# ble-v-monitor.net
KiCad netlist of a schematic drawn in EAGLE
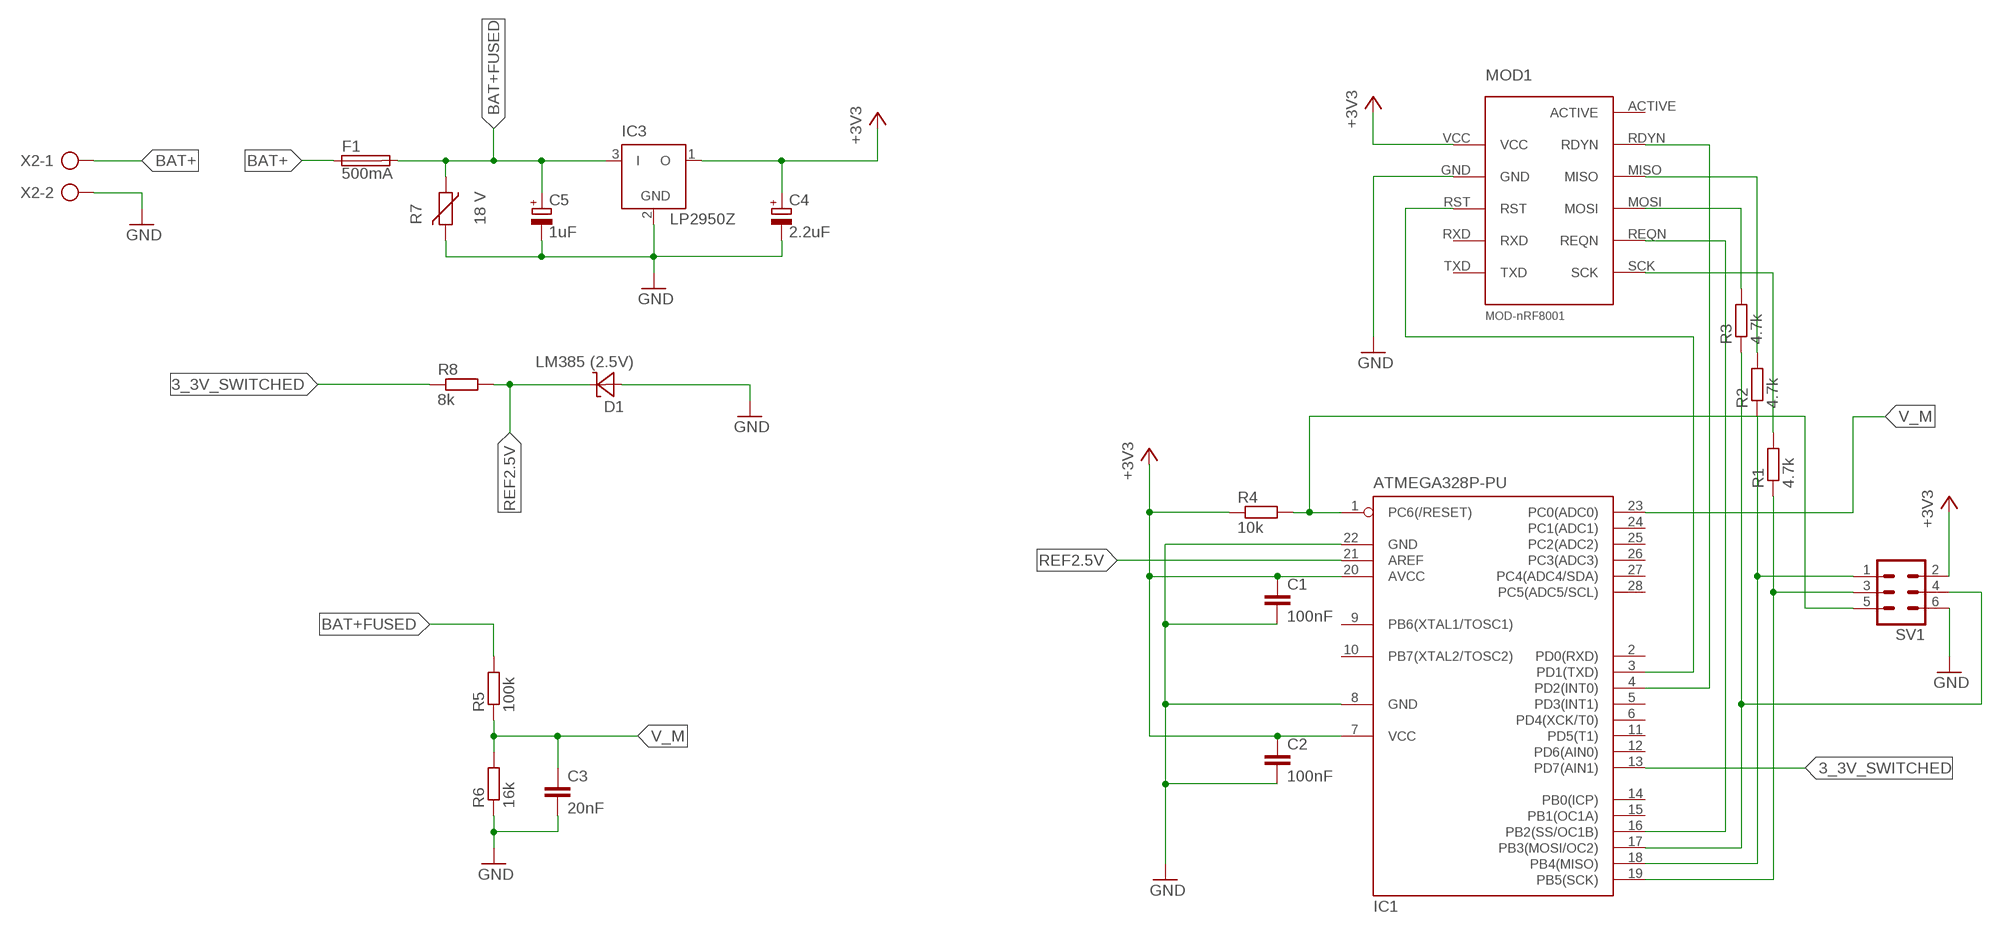
[diagram p0: schematic, sheet 1]

(export (version "E")
  (design (tool "Eeschema 10.0.6"))
  (components
    (comp (ref "C1")
      (value "100nF")
      (footprint "eagle-import:C050-024X044")
      (libsource (lib "eagle-import") (part "C-EU050-024X044"))
    )
    (comp (ref "C2")
      (value "100nF")
      (footprint "eagle-import:C050-024X044")
      (libsource (lib "eagle-import") (part "C-EU050-024X044"))
    )
    (comp (ref "C3")
      (value "20nF")
      (footprint "eagle-import:C050-024X044")
      (libsource (lib "eagle-import") (part "C-EU050-024X044"))
    )
    (comp (ref "C4")
      (value "2.2uF")
      (footprint "eagle-import:TT2D5")
      (libsource (lib "eagle-import") (part "CPOL-EUTT2D5"))
    )
    (comp (ref "C5")
      (value "1uF")
      (footprint "eagle-import:TT2D5")
      (libsource (lib "eagle-import") (part "CPOL-EUTT2D5"))
    )
    (comp (ref "D1")
      (value "LM385 (2.5V)")
      (footprint "eagle-import:TO-92")
      (libsource (lib "eagle-import") (part "LM385"))
    )
    (comp (ref "F1")
      (value "500mA")
      (footprint "eagle-import:SH22,5")
      (fields (field (name "MF") "SCHURTER") (field (name "MPN") "0031.8201"))
      (libsource (lib "eagle-import") (part "SH22,5"))
    )
    (comp (ref "IC1")
      (value "ATMEGA328P-PU")
      (footprint "eagle-import:DIL28-3")
      (libsource (lib "eagle-import") (part "MEGA8-P"))
    )
    (comp (ref "IC3")
      (value "LP2950Z")
      (footprint "eagle-import:TO92")
      (libsource (lib "eagle-import") (part "LP2950Z"))
    )
    (comp (ref "MOD1")
      (value "MOD-NRF8001MOD-NRF8001")
      (footprint "eagle-import:MOD-NRF8001")
      (libsource (lib "eagle-import") (part "MOD-NRF8001MOD-NRF8001"))
    )
    (comp (ref "R1")
      (value "4.7k")
      (footprint "eagle-import:0207_7")
      (libsource (lib "eagle-import") (part "R-EU_0207/7"))
    )
    (comp (ref "R2")
      (value "4.7k")
      (footprint "eagle-import:0207_7")
      (libsource (lib "eagle-import") (part "R-EU_0207/7"))
    )
    (comp (ref "R3")
      (value "4.7k")
      (footprint "eagle-import:0207_7")
      (libsource (lib "eagle-import") (part "R-EU_0207/7"))
    )
    (comp (ref "R4")
      (value "10k")
      (footprint "eagle-import:0207_7")
      (libsource (lib "eagle-import") (part "R-EU_0207/7"))
    )
    (comp (ref "R5")
      (value "100k")
      (footprint "eagle-import:0207_7")
      (libsource (lib "eagle-import") (part "R-EU_0207/7"))
    )
    (comp (ref "R6")
      (value "16k")
      (footprint "eagle-import:0207_7")
      (libsource (lib "eagle-import") (part "R-EU_0207/7"))
    )
    (comp (ref "R7")
      (value "18 V")
      (footprint "eagle-import:CT_CN0805")
      (libsource (lib "eagle-import") (part "VARISTORCN0805"))
    )
    (comp (ref "R8")
      (value "8k")
      (footprint "eagle-import:0207_7")
      (libsource (lib "eagle-import") (part "R-EU_0207/7"))
    )
    (comp (ref "SV1")
      (value "MA03-2")
      (footprint "eagle-import:MA03-2")
      (libsource (lib "eagle-import") (part "MA03-2"))
    )
    (comp (ref "X2")
      (value "AK500/2")
      (footprint "eagle-import:AK500_2")
      (libsource (lib "eagle-import") (part "AK500/2"))
    )
  )
  (nets
    (net (code "1") (name "+3V3") (class "Default")
      (node (ref "C1") (pin "1") (pinfunction "1_1") (pintype "passive"))
      (node (ref "C2") (pin "1") (pinfunction "1_1") (pintype "passive"))
      (node (ref "C4") (pin "+") (pinfunction "+_+") (pintype "passive"))
      (node (ref "IC1") (pin "20") (pinfunction "AVCC_20") (pintype "power_in"))
      (node (ref "IC1") (pin "7") (pinfunction "VCC_7") (pintype "power_in"))
      (node (ref "IC3") (pin "1") (pinfunction "O_1") (pintype "input"))
      (node (ref "MOD1") (pin "VCC") (pinfunction "VCC_VCC") (pintype "power_in"))
      (node (ref "R4") (pin "1") (pinfunction "1_1") (pintype "passive"))
      (node (ref "SV1") (pin "2") (pinfunction "2_2") (pintype "passive"))
    )
    (net (code "2") (name "3_3V_SWITCHED") (class "Default")
      (node (ref "IC1") (pin "13") (pinfunction "PD7(AIN1)_13") (pintype "bidirectional"))
      (node (ref "R8") (pin "1") (pinfunction "1_1") (pintype "passive"))
    )
    (net (code "3") (name "BAT+") (class "Default")
      (node (ref "F1") (pin "1") (pinfunction "1_1") (pintype "passive"))
      (node (ref "X2") (pin "1") (pinfunction "KL_1") (pintype "passive"))
    )
    (net (code "4") (name "BAT+FUSED") (class "Default")
      (node (ref "C5") (pin "+") (pinfunction "+_+") (pintype "passive"))
      (node (ref "F1") (pin "2") (pinfunction "2_2") (pintype "passive"))
      (node (ref "IC3") (pin "3") (pinfunction "I_3") (pintype "input"))
      (node (ref "R5") (pin "2") (pinfunction "2_2") (pintype "passive"))
      (node (ref "R7") (pin "1") (pinfunction "1_1") (pintype "passive"))
    )
    (net (code "5") (name "GND") (class "Default")
      (node (ref "C1") (pin "2") (pinfunction "2_2") (pintype "passive"))
      (node (ref "C2") (pin "2") (pinfunction "2_2") (pintype "passive"))
      (node (ref "C3") (pin "2") (pinfunction "2_2") (pintype "passive"))
      (node (ref "C4") (pin "-") (pinfunction "-_-") (pintype "passive"))
      (node (ref "C5") (pin "-") (pinfunction "-_-") (pintype "passive"))
      (node (ref "D1") (pin "+") (pinfunction "+_+") (pintype "passive"))
      (node (ref "IC1") (pin "22") (pinfunction "GND_22") (pintype "power_in"))
      (node (ref "IC1") (pin "8") (pinfunction "GND_8") (pintype "power_in"))
      (node (ref "IC3") (pin "2") (pinfunction "GND_2") (pintype "power_in"))
      (node (ref "MOD1") (pin "GND") (pinfunction "GND_GND") (pintype "power_in"))
      (node (ref "R6") (pin "1") (pinfunction "1_1") (pintype "passive"))
      (node (ref "R7") (pin "2") (pinfunction "2_2") (pintype "passive"))
      (node (ref "SV1") (pin "6") (pinfunction "6_6") (pintype "passive"))
      (node (ref "X2") (pin "2") (pinfunction "KL_2") (pintype "passive"))
    )
    (net (code "6") (name "Net-(IC1-PB2(SS{slash}OC1B))") (class "Default")
      (node (ref "IC1") (pin "16") (pinfunction "PB2(SS/OC1B)_16") (pintype "bidirectional"))
      (node (ref "MOD1") (pin "REQN") (pinfunction "REQN_REQN") (pintype "input"))
    )
    (net (code "7") (name "Net-(IC1-PB3(MOSI{slash}OC2))") (class "Default")
      (node (ref "IC1") (pin "17") (pinfunction "PB3(MOSI/OC2)_17") (pintype "bidirectional"))
      (node (ref "R3") (pin "1") (pinfunction "1_1") (pintype "passive"))
      (node (ref "SV1") (pin "4") (pinfunction "4_4") (pintype "passive"))
    )
    (net (code "8") (name "Net-(IC1-PB4(MISO))") (class "Default")
      (node (ref "IC1") (pin "18") (pinfunction "PB4(MISO)_18") (pintype "bidirectional"))
      (node (ref "R2") (pin "1") (pinfunction "1_1") (pintype "passive"))
      (node (ref "SV1") (pin "1") (pinfunction "1_1") (pintype "passive"))
    )
    (net (code "9") (name "Net-(IC1-PB5(SCK))") (class "Default")
      (node (ref "IC1") (pin "19") (pinfunction "PB5(SCK)_19") (pintype "bidirectional"))
      (node (ref "R1") (pin "1") (pinfunction "1_1") (pintype "passive"))
      (node (ref "SV1") (pin "3") (pinfunction "3_3") (pintype "passive"))
    )
    (net (code "10") (name "Net-(IC1-PC6({slash}RESET))") (class "Default")
      (node (ref "IC1") (pin "1") (pinfunction "PC6(/RESET)_1") (pintype "bidirectional"))
      (node (ref "R4") (pin "2") (pinfunction "2_2") (pintype "passive"))
      (node (ref "SV1") (pin "5") (pinfunction "5_5") (pintype "passive"))
    )
    (net (code "11") (name "Net-(IC1-PD1(TXD))") (class "Default")
      (node (ref "IC1") (pin "3") (pinfunction "PD1(TXD)_3") (pintype "bidirectional"))
      (node (ref "MOD1") (pin "RST") (pinfunction "RST_RST") (pintype "input"))
    )
    (net (code "12") (name "Net-(IC1-PD2(INT0))") (class "Default")
      (node (ref "IC1") (pin "4") (pinfunction "PD2(INT0)_4") (pintype "bidirectional"))
      (node (ref "MOD1") (pin "RDYN") (pinfunction "RDYN_RDYN") (pintype "output"))
    )
    (net (code "13") (name "Net-(MOD1-PadMISO)") (class "Default")
      (node (ref "MOD1") (pin "MISO") (pinfunction "MISO_MISO") (pintype "output"))
      (node (ref "R2") (pin "2") (pinfunction "2_2") (pintype "passive"))
    )
    (net (code "14") (name "Net-(MOD1-PadMOSI)") (class "Default")
      (node (ref "MOD1") (pin "MOSI") (pinfunction "MOSI_MOSI") (pintype "input"))
      (node (ref "R3") (pin "2") (pinfunction "2_2") (pintype "passive"))
    )
    (net (code "15") (name "Net-(MOD1-PadSCK)") (class "Default")
      (node (ref "MOD1") (pin "SCK") (pinfunction "SCK_SCK") (pintype "input"))
      (node (ref "R1") (pin "2") (pinfunction "2_2") (pintype "passive"))
    )
    (net (code "16") (name "REF2.5V") (class "Default")
      (node (ref "D1") (pin "-") (pinfunction "-_-") (pintype "passive"))
      (node (ref "IC1") (pin "21") (pinfunction "AREF_21") (pintype "passive"))
      (node (ref "R8") (pin "2") (pinfunction "2_2") (pintype "passive"))
    )
    (net (code "17") (name "V_M") (class "Default")
      (node (ref "C3") (pin "1") (pinfunction "1_1") (pintype "passive"))
      (node (ref "IC1") (pin "23") (pinfunction "PC0(ADC0)_23") (pintype "bidirectional"))
      (node (ref "R5") (pin "1") (pinfunction "1_1") (pintype "passive"))
      (node (ref "R6") (pin "2") (pinfunction "2_2") (pintype "passive"))
    )
    (net (code "18") (name "unconnected-(IC1-PB0(ICP)-Pad14)") (class "Default")
      (node (ref "IC1") (pin "14") (pinfunction "PB0(ICP)_14") (pintype "bidirectional"))
    )
    (net (code "19") (name "unconnected-(IC1-PB1(OC1A)-Pad15)") (class "Default")
      (node (ref "IC1") (pin "15") (pinfunction "PB1(OC1A)_15") (pintype "bidirectional"))
    )
    (net (code "20") (name "unconnected-(IC1-PB6(XTAL1{slash}TOSC1)-Pad9)") (class "Default")
      (node (ref "IC1") (pin "9") (pinfunction "PB6(XTAL1/TOSC1)_9") (pintype "bidirectional"))
    )
    (net (code "21") (name "unconnected-(IC1-PB7(XTAL2{slash}TOSC2)-Pad10)") (class "Default")
      (node (ref "IC1") (pin "10") (pinfunction "PB7(XTAL2/TOSC2)_10") (pintype "bidirectional"))
    )
    (net (code "22") (name "unconnected-(IC1-PC1(ADC1)-Pad24)") (class "Default")
      (node (ref "IC1") (pin "24") (pinfunction "PC1(ADC1)_24") (pintype "bidirectional"))
    )
    (net (code "23") (name "unconnected-(IC1-PC2(ADC2)-Pad25)") (class "Default")
      (node (ref "IC1") (pin "25") (pinfunction "PC2(ADC2)_25") (pintype "bidirectional"))
    )
    (net (code "24") (name "unconnected-(IC1-PC3(ADC3)-Pad26)") (class "Default")
      (node (ref "IC1") (pin "26") (pinfunction "PC3(ADC3)_26") (pintype "bidirectional"))
    )
    (net (code "25") (name "unconnected-(IC1-PC4(ADC4{slash}SDA)-Pad27)") (class "Default")
      (node (ref "IC1") (pin "27") (pinfunction "PC4(ADC4/SDA)_27") (pintype "bidirectional"))
    )
    (net (code "26") (name "unconnected-(IC1-PC5(ADC5{slash}SCL)-Pad28)") (class "Default")
      (node (ref "IC1") (pin "28") (pinfunction "PC5(ADC5/SCL)_28") (pintype "bidirectional"))
    )
    (net (code "27") (name "unconnected-(IC1-PD0(RXD)-Pad2)") (class "Default")
      (node (ref "IC1") (pin "2") (pinfunction "PD0(RXD)_2") (pintype "bidirectional"))
    )
    (net (code "28") (name "unconnected-(IC1-PD3(INT1)-Pad5)") (class "Default")
      (node (ref "IC1") (pin "5") (pinfunction "PD3(INT1)_5") (pintype "bidirectional"))
    )
    (net (code "29") (name "unconnected-(IC1-PD4(XCK{slash}T0)-Pad6)") (class "Default")
      (node (ref "IC1") (pin "6") (pinfunction "PD4(XCK/T0)_6") (pintype "bidirectional"))
    )
    (net (code "30") (name "unconnected-(IC1-PD5(T1)-Pad11)") (class "Default")
      (node (ref "IC1") (pin "11") (pinfunction "PD5(T1)_11") (pintype "bidirectional"))
    )
    (net (code "31") (name "unconnected-(IC1-PD6(AIN0)-Pad12)") (class "Default")
      (node (ref "IC1") (pin "12") (pinfunction "PD6(AIN0)_12") (pintype "bidirectional"))
    )
    (net (code "32") (name "unconnected-(MOD1-PadACTIVE)") (class "Default")
      (node (ref "MOD1") (pin "ACTIVE") (pinfunction "ACTIVE_ACTIVE") (pintype "output"))
    )
    (net (code "33") (name "unconnected-(MOD1-PadRXD)") (class "Default")
      (node (ref "MOD1") (pin "RXD") (pinfunction "RXD_RXD") (pintype "input"))
    )
    (net (code "34") (name "unconnected-(MOD1-PadTXD)") (class "Default")
      (node (ref "MOD1") (pin "TXD") (pinfunction "TXD_TXD") (pintype "output"))
    )
  )
)
